# SHO.net
KiCad netlist of a schematic drawn in EAGLE
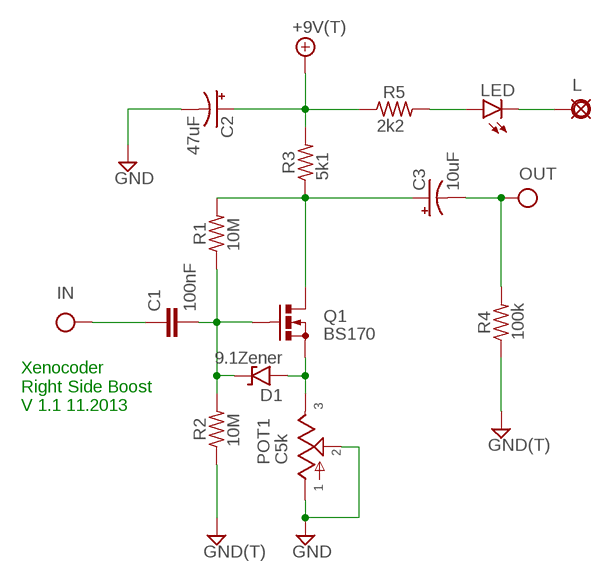
[diagram p0: schematic, sheet 1]

(export (version "E")
  (design (tool "Eeschema 10.0.6"))
  (components
    (comp (ref "+9V")
      (value "+9V(T)")
      (footprint "eagle-import:SQUARE")
      (libsource (lib "eagle-import") (part "+9V(T)"))
    )
    (comp (ref "C1")
      (value "100nF")
      (footprint "eagle-import:075X030")
      (libsource (lib "eagle-import") (part "075X0302"))
    )
    (comp (ref "C2")
      (value "47uF")
      (footprint "eagle-import:063_025")
      (libsource (lib "eagle-import") (part "0631"))
    )
    (comp (ref "C3")
      (value "10uF")
      (footprint "eagle-import:063_025")
      (libsource (lib "eagle-import") (part "0631"))
    )
    (comp (ref "D1")
      (value "9.1Zener")
      (footprint "eagle-import:DO35-3")
      (libsource (lib "eagle-import") (part "1N9ZENER"))
    )
    (comp (ref "G")
      (value "GND(T)")
      (footprint "eagle-import:SQUARE")
      (libsource (lib "eagle-import") (part "GND(T)"))
    )
    (comp (ref "GND")
      (value "GND(T)")
      (footprint "eagle-import:SQUARE")
      (libsource (lib "eagle-import") (part "GND(T)"))
    )
    (comp (ref "IN")
      (value "IN(T)")
      (footprint "eagle-import:SQUARE")
      (libsource (lib "eagle-import") (part "IN(T)"))
    )
    (comp (ref "L")
      (value "3mm")
      (footprint "eagle-import:SQUARE")
      (libsource (lib "eagle-import") (part "PAD"))
    )
    (comp (ref "LED")
      (value "LED3MM")
      (footprint "eagle-import:LED3MM")
      (libsource (lib "eagle-import") (part "LED3MM"))
    )
    (comp (ref "OUT")
      (value "OUT(T)")
      (footprint "eagle-import:SQUARE")
      (libsource (lib "eagle-import") (part "OUT(T)"))
    )
    (comp (ref "POT1")
      (value "C5k")
      (footprint "eagle-import:16MM_PCB_PADS")
      (libsource (lib "eagle-import") (part "POT16MM_PCB_PADS"))
    )
    (comp (ref "Q1")
      (value "BS170")
      (footprint "eagle-import:SOT54ES")
      (libsource (lib "eagle-import") (part "BS170"))
    )
    (comp (ref "R1")
      (value "10M")
      (footprint "eagle-import:R0207_3")
      (libsource (lib "eagle-import") (part "6MM.3"))
    )
    (comp (ref "R2")
      (value "10M")
      (footprint "eagle-import:R0207_3")
      (libsource (lib "eagle-import") (part "6MM.3"))
    )
    (comp (ref "R3")
      (value "5k1")
      (footprint "eagle-import:R0207_3")
      (libsource (lib "eagle-import") (part "6MM.3"))
    )
    (comp (ref "R4")
      (value "100k")
      (footprint "eagle-import:R0207_3")
      (libsource (lib "eagle-import") (part "6MM.3"))
    )
    (comp (ref "R5")
      (value "2k2")
      (footprint "eagle-import:R0207_3")
      (libsource (lib "eagle-import") (part "6MM.3"))
    )
  )
  (nets
    (net (code "1") (name "+9V(T)") (class "Default")
      (node (ref "+9V") (pin "1") (pinfunction "+9V_1") (pintype "power_in"))
      (node (ref "C2") (pin "+") (pinfunction "+_+") (pintype "passive"))
      (node (ref "R3") (pin "2") (pinfunction "2_2") (pintype "passive"))
      (node (ref "R5") (pin "1") (pinfunction "1_1") (pintype "passive"))
    )
    (net (code "2") (name "GND") (class "Default")
      (node (ref "C2") (pin "-") (pinfunction "-_-") (pintype "passive"))
      (node (ref "G") (pin "1") (pinfunction "GND_1") (pintype "power_in"))
      (node (ref "GND") (pin "1") (pinfunction "GND_1") (pintype "power_in"))
      (node (ref "POT1") (pin "1") (pinfunction "1_1") (pintype "passive"))
      (node (ref "POT1") (pin "2") (pinfunction "2_2") (pintype "passive"))
      (node (ref "R2") (pin "1") (pinfunction "1_1") (pintype "passive"))
      (node (ref "R4") (pin "1") (pinfunction "1_1") (pintype "passive"))
    )
    (net (code "3") (name "IN(T)") (class "Default")
      (node (ref "C1") (pin "1") (pinfunction "1_1") (pintype "passive"))
      (node (ref "IN") (pin "1") (pinfunction "IN_1") (pintype "power_in"))
    )
    (net (code "4") (name "Net-(C1-Pad2)") (class "Default")
      (node (ref "C1") (pin "2") (pinfunction "2_2") (pintype "passive"))
      (node (ref "D1") (pin "C") (pinfunction "C_C") (pintype "passive"))
      (node (ref "Q1") (pin "G") (pinfunction "G_G") (pintype "passive"))
      (node (ref "R1") (pin "1") (pinfunction "1_1") (pintype "passive"))
      (node (ref "R2") (pin "2") (pinfunction "2_2") (pintype "passive"))
    )
    (net (code "5") (name "Net-(C3-Pad+)") (class "Default")
      (node (ref "C3") (pin "+") (pinfunction "+_+") (pintype "passive"))
      (node (ref "Q1") (pin "D") (pinfunction "D_D") (pintype "passive"))
      (node (ref "R1") (pin "2") (pinfunction "2_2") (pintype "passive"))
      (node (ref "R3") (pin "1") (pinfunction "1_1") (pintype "passive"))
    )
    (net (code "6") (name "Net-(D1-PadA)") (class "Default")
      (node (ref "D1") (pin "A") (pinfunction "A_A") (pintype "passive"))
      (node (ref "POT1") (pin "3") (pinfunction "3_3") (pintype "passive"))
      (node (ref "Q1") (pin "S") (pinfunction "S_S") (pintype "passive"))
    )
    (net (code "7") (name "Net-(L-PAD)") (class "Default")
      (node (ref "L") (pin "1") (pinfunction "PAD_1") (pintype "passive"))
      (node (ref "LED") (pin "K") (pinfunction "C_K") (pintype "passive"))
    )
    (net (code "8") (name "Net-(LED-PadA)") (class "Default")
      (node (ref "LED") (pin "A") (pinfunction "A_A") (pintype "passive"))
      (node (ref "R5") (pin "2") (pinfunction "2_2") (pintype "passive"))
    )
    (net (code "9") (name "OUT(T)") (class "Default")
      (node (ref "C3") (pin "-") (pinfunction "-_-") (pintype "passive"))
      (node (ref "OUT") (pin "1") (pinfunction "OUT_1") (pintype "power_in"))
      (node (ref "R4") (pin "2") (pinfunction "2_2") (pintype "passive"))
    )
  )
)
